# communication.net
KiCad netlist of a schematic drawn in Altium Designer
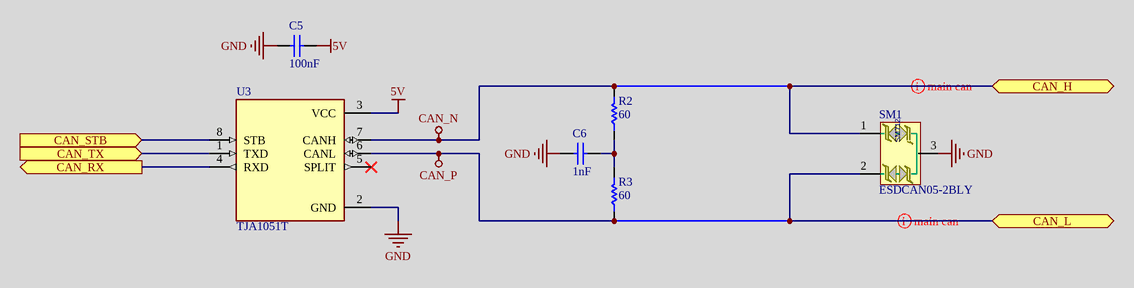
[diagram p0: communication.SchDoc]

(export (version "E")
  (design (tool "Eeschema 10.0.6"))
  (components
    (comp (ref "C5")
      (value "100nF")
      (footprint "eLIB:CAPC0603")
      (description "Capacitor")
      (fields (field (name "PUBLISHER") "Altium Limited"))
      (libsource (lib "TaraSchlib") (part "Cap"))
    )
    (comp (ref "C6")
      (value "1nF")
      (footprint "eLIB:CAPC0603")
      (description "Capacitor")
      (fields (field (name "PUBLISHER") "Altium Limited"))
      (libsource (lib "TaraSchlib") (part "Cap"))
    )
    (comp (ref "R2")
      (value "60")
      (footprint "RESC0603")
      (description "Resistor")
      (fields (field (name "TOLERANCE") "5%") (field (name "POWER") "1/8 W"))
      (libsource (lib "TaraSchlib") (part "Resistor"))
    )
    (comp (ref "R3")
      (value "60")
      (footprint "RESC0603")
      (description "Resistor")
      (fields (field (name "TOLERANCE") "5%") (field (name "POWER") "1/8 W"))
      (libsource (lib "TaraSchlib") (part "Resistor"))
    )
    (comp (ref "SM1")
      (value "ESDCAN05-2BLY")
      (footprint "SOT-23_N")
      (description "Asymmetrical TVS Diode for Extended Common-Mode RS-485")
      (libsource (lib "TaraSchlib") (part "SM712"))
    )
    (comp (ref "U3")
      (value "TJA1051T")
      (footprint "LM358")
      (description "1/1 Transceiver Half CANbus 8-SO")
      (fields (field (name "MF") "NXP USA") (field (name "MP") "TJA1040"))
      (libsource (lib "TaraSchlib") (part "TJA1040"))
    )
  )
  (nets
    (net (code "1") (name "/CAN_RX") (class "Default")
      (node (ref "U3") (pin "4") (pinfunction "RXD_4") (pintype "output"))
    )
    (net (code "2") (name "/CAN_STB") (class "Default")
      (node (ref "U3") (pin "8") (pinfunction "STB_8") (pintype "input"))
    )
    (net (code "3") (name "/CAN_TX") (class "Default")
      (node (ref "U3") (pin "1") (pinfunction "TXD_1") (pintype "input"))
    )
    (net (code "4") (name "5V") (class "Default")
      (node (ref "C5") (pin "1") (pinfunction "1_1") (pintype "passive"))
      (node (ref "U3") (pin "3") (pinfunction "VCC_3") (pintype "power_in"))
    )
    (net (code "5") (name "CAN_N") (class "Default")
      (node (ref "R2") (pin "2") (pinfunction "2_2") (pintype "passive"))
      (node (ref "SM1") (pin "1") (pinfunction "1_1") (pintype "passive"))
      (node (ref "U3") (pin "7") (pinfunction "CANH_7") (pintype "bidirectional"))
    )
    (net (code "6") (name "CAN_P") (class "Default")
      (node (ref "R3") (pin "1") (pinfunction "1_1") (pintype "passive"))
      (node (ref "SM1") (pin "2") (pinfunction "2_2") (pintype "passive"))
      (node (ref "U3") (pin "6") (pinfunction "CANL_6") (pintype "bidirectional"))
    )
    (net (code "7") (name "GND") (class "Default")
      (node (ref "C5") (pin "2") (pinfunction "2_2") (pintype "passive"))
      (node (ref "C6") (pin "2") (pinfunction "2_2") (pintype "passive"))
      (node (ref "SM1") (pin "3") (pinfunction "3_3") (pintype "passive"))
      (node (ref "U3") (pin "2") (pinfunction "GND_2") (pintype "power_in"))
    )
    (net (code "8") (name "Net-(C6-Pad1)") (class "Default")
      (node (ref "C6") (pin "1") (pinfunction "1_1") (pintype "passive"))
      (node (ref "R2") (pin "1") (pinfunction "1_1") (pintype "passive"))
      (node (ref "R3") (pin "2") (pinfunction "2_2") (pintype "passive"))
    )
    (net (code "9") (name "unconnected-(U3-SPLIT-Pad5)") (class "Default")
      (node (ref "U3") (pin "5") (pinfunction "SPLIT_5") (pintype "output+no_connect"))
    )
  )
)
